# XIAO-HAT-3.net
KiCad netlist of a schematic drawn in Altium Designer
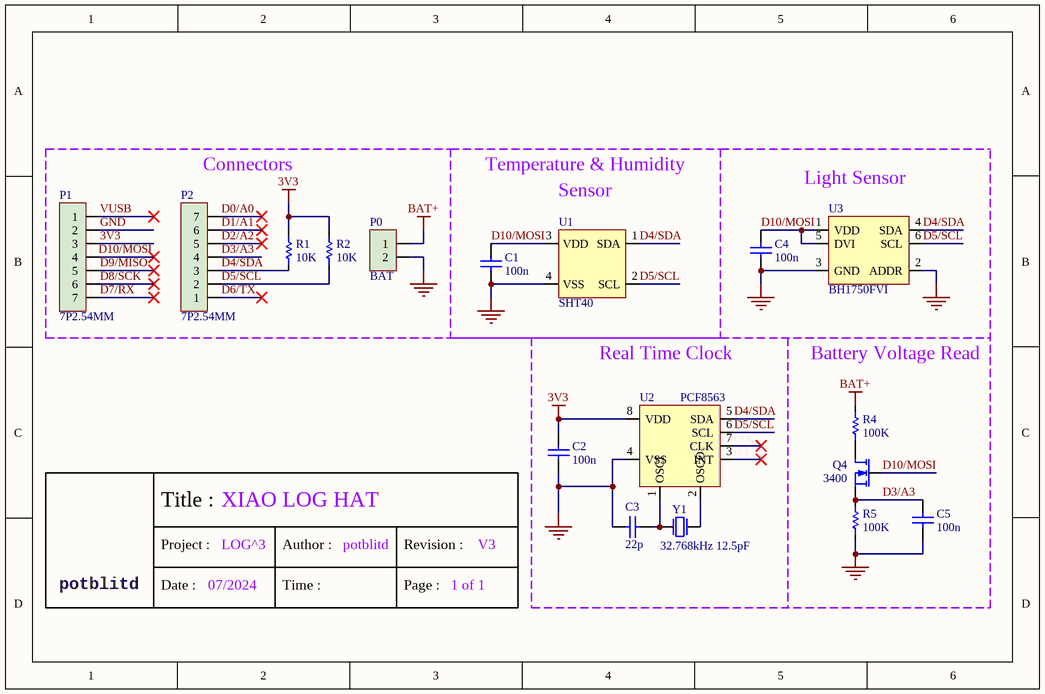
[diagram p0: XIAO-HAT-3.SchDoc]

(export (version "E")
  (design (tool "Eeschema 10.0.6"))
  (components
    (comp (ref "C1")
      (value "100n")
      (footprint "0603C-BOX")
      (description "Capacitor 100nF ±10% 50V")
      (fields (field (name "MANUFACTURER") "Samsung") (field (name "Comment") "Capacitor"))
      (libsource (lib "Simulation Generic Components") (part "Capacitor"))
    )
    (comp (ref "C2")
      (value "100n")
      (footprint "0603C-BOX")
      (description "Capacitor 100nF ±10% 50V")
      (fields (field (name "MANUFACTURER") "Samsung") (field (name "Comment") "Capacitor"))
      (libsource (lib "Simulation Generic Components") (part "Capacitor"))
    )
    (comp (ref "C3")
      (value "22p")
      (footprint "0603C-BOX")
      (description "Capacitor 22pF ±5% 50V")
      (fields (field (name "MANUFACTURER") "Samsung") (field (name "Comment") "Capacitor"))
      (libsource (lib "Simulation Generic Components") (part "Capacitor"))
    )
    (comp (ref "C4")
      (value "100n")
      (footprint "0603C-BOX")
      (description "Capacitor 100nF ±10% 50V")
      (fields (field (name "MANUFACTURER") "Samsung") (field (name "Comment") "Capacitor"))
      (libsource (lib "Simulation Generic Components") (part "Capacitor"))
    )
    (comp (ref "C5")
      (value "100n")
      (footprint "0603C-BOX")
      (description "Capacitor 100nF ±10% 50V")
      (fields (field (name "MANUFACTURER") "Samsung") (field (name "Comment") "Capacitor"))
      (libsource (lib "Simulation Generic Components") (part "Capacitor"))
    )
    (comp (ref "P0")
      (value "BAT")
      (footprint "2P-2.54mm-NOSILK")
      (description "General 2-pin connection")
      (libsource (lib "AltiumLib") (part "2-pins Header"))
    )
    (comp (ref "P1")
      (value "7P2.54MM")
      (footprint "7P-2.54mm-XIAO")
      (description "General 7-pin connection")
      (libsource (lib "") (part "7-pins Header_1"))
    )
    (comp (ref "P2")
      (value "7P2.54MM")
      (footprint "7P-2.54mm-XIAO")
      (description "General 7-pin connection")
      (libsource (lib "AltiumLib") (part "7-pins Header"))
    )
    (comp (ref "Q4")
      (value "3400")
      (footprint "SOT23-3 M")
      (description "MOSFET N-channel 30V 5.7A")
      (fields (field (name "MANUFACTURER") "UMW(友台半导体)"))
      (libsource (lib "AltiumLib") (part "MOSFET-N"))
    )
    (comp (ref "R1")
      (value "10K")
      (footprint "0603R-BOX")
      (description "Resistor 10kΩ ±1% 1/16W")
      (fields (field (name "MANUFACTURER") "UNI-ROYAL(厚声)") (field (name "Comment") "Resistor"))
      (libsource (lib "Simulation Generic Components") (part "RES"))
    )
    (comp (ref "R2")
      (value "10K")
      (footprint "0603R-BOX")
      (description "Resistor 10kΩ ±1% 1/16W")
      (fields (field (name "MANUFACTURER") "UNI-ROYAL(厚声)") (field (name "Comment") "Resistor"))
      (libsource (lib "Simulation Generic Components") (part "RES"))
    )
    (comp (ref "R4")
      (value "100K")
      (footprint "0603R-BOX")
      (description "Resistor 100kΩ ±1% 100mW")
      (fields (field (name "MANUFACTURER") "UNI-ROYAL(厚声)") (field (name "Comment") "Resistor"))
      (libsource (lib "Simulation Generic Components") (part "RES"))
    )
    (comp (ref "R5")
      (value "100K")
      (footprint "0603R-BOX")
      (description "Resistor 100kΩ ±1% 100mW")
      (fields (field (name "MANUFACTURER") "UNI-ROYAL(厚声)") (field (name "Comment") "Resistor"))
      (libsource (lib "Simulation Generic Components") (part "RES"))
    )
    (comp (ref "U1")
      (value "SHT40")
      (footprint "DFN-4-EP(1.5x1.5)-BOX")
      (description "SHT40 temperature and humidity sensor")
      (fields (field (name "MANUFACTURER") "Sensirion(瑞士盛思锐)"))
      (libsource (lib "AltiumLib") (part "SHT40"))
    )
    (comp (ref "U2")
      (value "PCF8563")
      (footprint "SOP-8 M")
      (description "IC real-time clock with alarm interrupt")
      (fields (field (name "MANUFACTURER") "NXP"))
      (libsource (lib "AltiumLib") (part "RTC-8563"))
    )
    (comp (ref "U3")
      (value "BH1750FVI")
      (footprint "WSOF6 M")
      (description "Digital light sensor")
      (fields (field (name "MANUFACTURER") "ROHM"))
      (libsource (lib "AltiumLib") (part "BH1750"))
    )
    (comp (ref "Y1")
      (value "32.768kHz 12.5pF")
      (footprint "FC135 M")
      (description "Crystal oscillator 32.768kHz 20ppm 12.5pF")
      (fields (field (name "MANUFACTURER") "TKD") (field (name "Comment") "Oscillator"))
      (libsource (lib "AltiumLib") (part "XO-2"))
    )
  )
  (nets
    (net (code "1") (name "/CLK") (class "Default")
      (node (ref "U2") (pin "7") (pinfunction "CLK_7") (pintype "passive+no_connect"))
    )
    (net (code "2") (name "/D0{slash}A0") (class "Default")
      (node (ref "P2") (pin "7") (pinfunction "7_7") (pintype "passive+no_connect"))
    )
    (net (code "3") (name "/D1{slash}A1") (class "Default")
      (node (ref "P2") (pin "6") (pinfunction "6_6") (pintype "passive+no_connect"))
    )
    (net (code "4") (name "/D2{slash}A2") (class "Default")
      (node (ref "P2") (pin "5") (pinfunction "5_5") (pintype "passive+no_connect"))
    )
    (net (code "5") (name "/D3{slash}A3") (class "Default")
      (node (ref "C5") (pin "1") (pinfunction "1_1") (pintype "passive"))
      (node (ref "P2") (pin "4") (pinfunction "4_4") (pintype "passive"))
      (node (ref "Q4") (pin "2") (pinfunction "S_2") (pintype "passive"))
      (node (ref "R5") (pin "2") (pinfunction "2_2") (pintype "passive"))
    )
    (net (code "6") (name "/D4{slash}SDA") (class "Default")
      (node (ref "P2") (pin "3") (pinfunction "3_3") (pintype "passive"))
      (node (ref "R1") (pin "1") (pinfunction "1_1") (pintype "passive"))
      (node (ref "U1") (pin "1") (pinfunction "SDA_1") (pintype "passive"))
      (node (ref "U2") (pin "5") (pinfunction "SDA_5") (pintype "passive"))
      (node (ref "U3") (pin "4") (pinfunction "SDA_4") (pintype "passive"))
    )
    (net (code "7") (name "/D5{slash}SCL") (class "Default")
      (node (ref "P2") (pin "2") (pinfunction "2_2") (pintype "passive"))
      (node (ref "R2") (pin "1") (pinfunction "1_1") (pintype "passive"))
      (node (ref "U1") (pin "2") (pinfunction "SCL_2") (pintype "passive"))
      (node (ref "U2") (pin "6") (pinfunction "SCL_6") (pintype "passive"))
      (node (ref "U3") (pin "6") (pinfunction "SCL_6") (pintype "passive"))
    )
    (net (code "8") (name "/D6{slash}TX") (class "Default")
      (node (ref "P2") (pin "1") (pinfunction "1_1") (pintype "passive+no_connect"))
    )
    (net (code "9") (name "/D7{slash}RX") (class "Default")
      (node (ref "P1") (pin "7") (pinfunction "7_7") (pintype "passive+no_connect"))
    )
    (net (code "10") (name "/D8{slash}SCK") (class "Default")
      (node (ref "P1") (pin "6") (pinfunction "6_6") (pintype "passive+no_connect"))
    )
    (net (code "11") (name "/D9{slash}MISO") (class "Default")
      (node (ref "P1") (pin "5") (pinfunction "5_5") (pintype "passive+no_connect"))
    )
    (net (code "12") (name "/D10{slash}MOSI") (class "Default")
      (node (ref "C1") (pin "1") (pinfunction "1_1") (pintype "passive"))
      (node (ref "C4") (pin "1") (pinfunction "1_1") (pintype "passive"))
      (node (ref "P1") (pin "4") (pinfunction "4_4") (pintype "passive"))
      (node (ref "Q4") (pin "1") (pinfunction "G_1") (pintype "passive"))
      (node (ref "U1") (pin "3") (pinfunction "VDD_3") (pintype "passive"))
      (node (ref "U3") (pin "1") (pinfunction "VDD_1") (pintype "passive"))
      (node (ref "U3") (pin "5") (pinfunction "DVI_5") (pintype "passive"))
    )
    (net (code "13") (name "/INT") (class "Default")
      (node (ref "U2") (pin "3") (pinfunction "INT_3") (pintype "passive+no_connect"))
    )
    (net (code "14") (name "/VUSB") (class "Default")
      (node (ref "P1") (pin "1") (pinfunction "1_1") (pintype "passive+no_connect"))
    )
    (net (code "15") (name "3V3") (class "Default")
      (node (ref "C2") (pin "1") (pinfunction "1_1") (pintype "passive"))
      (node (ref "P1") (pin "3") (pinfunction "3_3") (pintype "passive"))
      (node (ref "R1") (pin "2") (pinfunction "2_2") (pintype "passive"))
      (node (ref "R2") (pin "2") (pinfunction "2_2") (pintype "passive"))
      (node (ref "U2") (pin "8") (pinfunction "VDD_8") (pintype "passive"))
    )
    (net (code "16") (name "BAT+") (class "Default")
      (node (ref "P0") (pin "1") (pinfunction "1_1") (pintype "passive"))
      (node (ref "R4") (pin "2") (pinfunction "2_2") (pintype "passive"))
    )
    (net (code "17") (name "GND") (class "Default")
      (node (ref "C1") (pin "2") (pinfunction "2_2") (pintype "passive"))
      (node (ref "C2") (pin "2") (pinfunction "2_2") (pintype "passive"))
      (node (ref "C3") (pin "2") (pinfunction "2_2") (pintype "passive"))
      (node (ref "C4") (pin "2") (pinfunction "2_2") (pintype "passive"))
      (node (ref "C5") (pin "2") (pinfunction "2_2") (pintype "passive"))
      (node (ref "P0") (pin "2") (pinfunction "2_2") (pintype "passive"))
      (node (ref "P1") (pin "2") (pinfunction "2_2") (pintype "passive"))
      (node (ref "R5") (pin "1") (pinfunction "1_1") (pintype "passive"))
      (node (ref "U1") (pin "4") (pinfunction "VSS_4") (pintype "passive"))
      (node (ref "U2") (pin "4") (pinfunction "VSS_4") (pintype "passive"))
      (node (ref "U3") (pin "2") (pinfunction "ADDR_2") (pintype "passive"))
      (node (ref "U3") (pin "3") (pinfunction "GND_3") (pintype "passive"))
    )
    (net (code "18") (name "Net-(Q4-D)") (class "Default")
      (node (ref "Q4") (pin "3") (pinfunction "D_3") (pintype "passive"))
      (node (ref "R4") (pin "1") (pinfunction "1_1") (pintype "passive"))
    )
    (net (code "19") (name "Net-(U2-OSCI)") (class "Default")
      (node (ref "C3") (pin "1") (pinfunction "1_1") (pintype "passive"))
      (node (ref "U2") (pin "1") (pinfunction "OSCI_1") (pintype "passive"))
      (node (ref "Y1") (pin "2") (pinfunction "2_2") (pintype "passive"))
    )
    (net (code "20") (name "Net-(U2-OSCO)") (class "Default")
      (node (ref "U2") (pin "2") (pinfunction "OSCO_2") (pintype "passive"))
      (node (ref "Y1") (pin "1") (pinfunction "1_1") (pintype "passive"))
    )
  )
)
